# Main_Board.net
KiCad netlist of a schematic drawn in Altium Designer
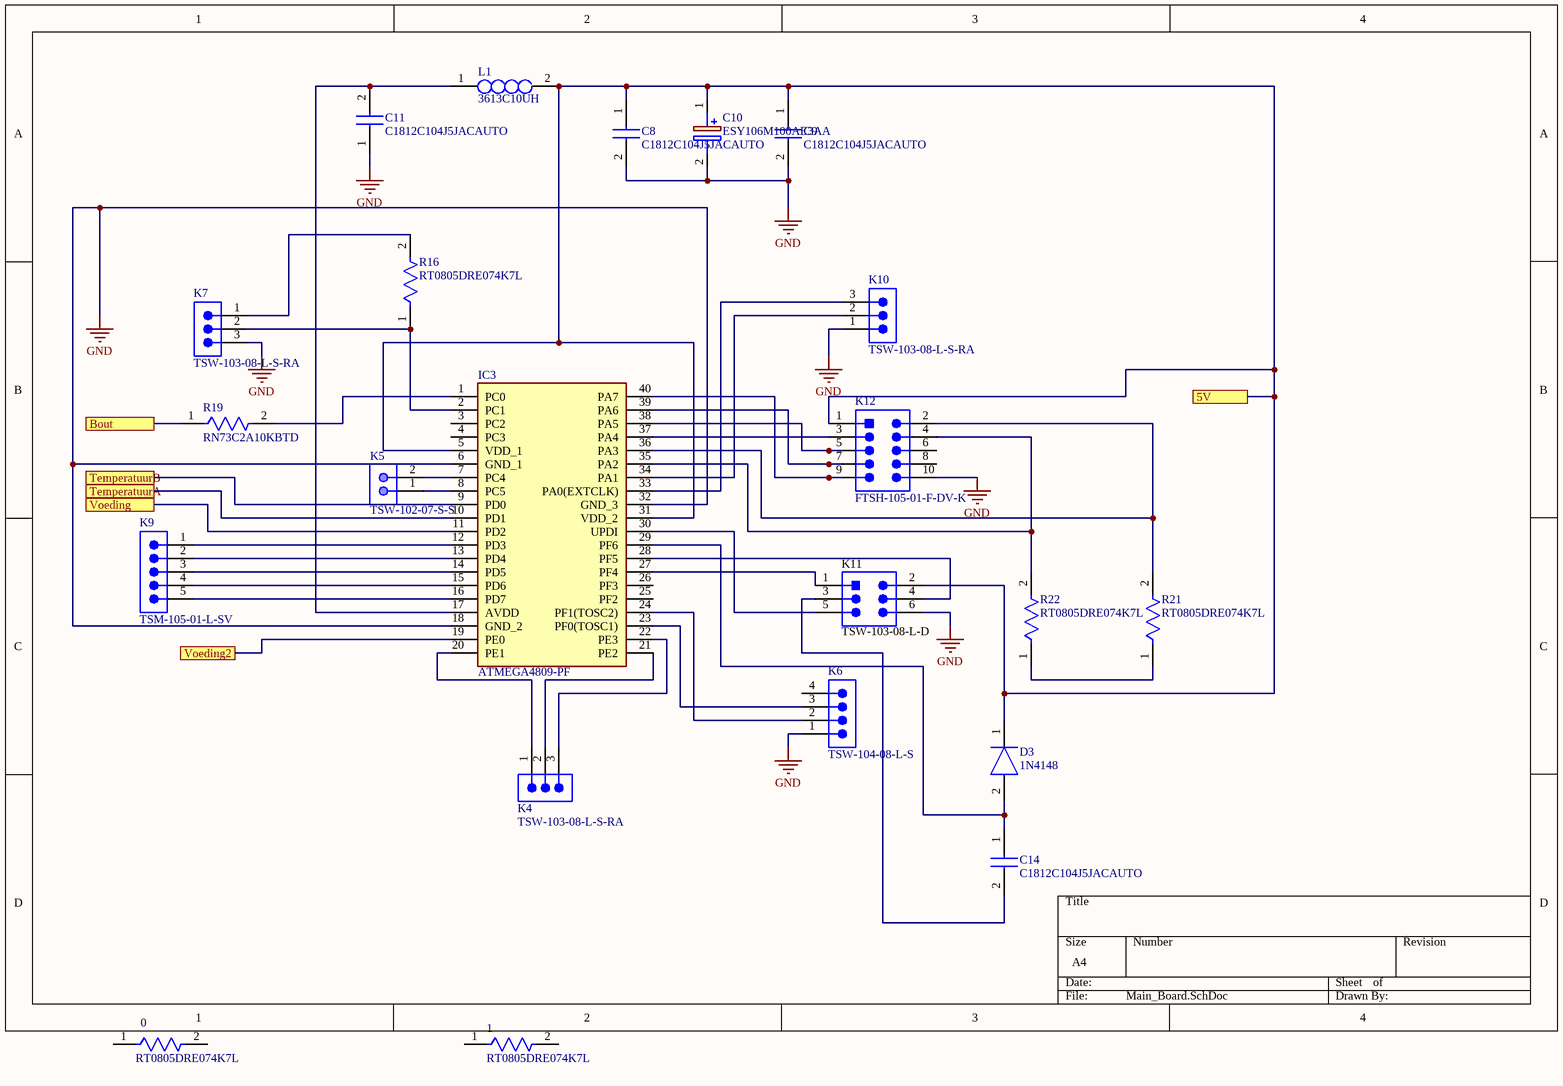
[diagram p0: Main_Board.SchDoc]

(export (version "E")
  (design (tool "Eeschema 10.0.6"))
  (components
    (comp (ref "0")
      (value "RT0805DRE074K7L")
      (footprint "FP-RT0805-MFG")
      (description "RES SMD 4.7K OHM 0.5% 1/8W 0805")
      (fields
        (field (name "OCTOPART") "https://octopart.com/rt0805dre074k7l-yageo-1242027")
        (field (name "TOLERANCE") "0.01")
      )
      (libsource (lib "Altium Content Vault") (part "1029c3af85768c4190bb7ad29bc67b5"))
    )
    (comp (ref "1")
      (value "RT0805DRE074K7L")
      (footprint "FP-RT0805-MFG")
      (description "RES SMD 4.7K OHM 0.5% 1/8W 0805")
      (fields
        (field (name "OCTOPART") "https://octopart.com/rt0805dre074k7l-yageo-1242027")
        (field (name "TOLERANCE") "0.01")
      )
      (libsource (lib "Altium Content Vault") (part "1029c3af85768c4190bb7ad29bc67b5"))
    )
    (comp (ref "C8")
      (value "C1812C104J5JACAUTO")
      (footprint "SamacSys:CAPC4532X110N")
      (description "Capacitor")
      (libsource (lib "*") (part "C1812C104J5JACAUTO"))
    )
    (comp (ref "C9")
      (value "C1812C104J5JACAUTO")
      (footprint "SamacSys:CAPC4532X110N")
      (description "Capacitor")
      (libsource (lib "*") (part "C1812C104J5JACAUTO"))
    )
    (comp (ref "C10")
      (value "ESY106M100AE3AA")
      (footprint "SamacSys:CAPPRD250W50D630H1250")
      (description "Capacitor Polarised")
      (libsource (lib "*") (part "ESY106M100AE3AA"))
    )
    (comp (ref "C11")
      (value "C1812C104J5JACAUTO")
      (footprint "SamacSys:CAPC4532X110N")
      (description "Capacitor")
      (libsource (lib "*") (part "C1812C104J5JACAUTO"))
    )
    (comp (ref "C14")
      (value "C1812C104J5JACAUTO")
      (footprint "SamacSys:CAPC4532X110N")
      (description "Capacitor")
      (libsource (lib "*") (part "C1812C104J5JACAUTO"))
    )
    (comp (ref "D3")
      (value "1N4148")
      (footprint "SamacSys:DIOAD1165W56L425D185")
      (description "Diode")
      (libsource (lib "*") (part "1N4148"))
    )
    (comp (ref "IC3")
      (value "ATMEGA4809-PF")
      (footprint "SamacSys:DIP1543W58P254L5175H635Q40N")
      (description "Integrated Circuit")
      (fields (field (name "MOUSER2 PART NUMBER") "556-ATMEGA4809-PF"))
      (libsource (lib "*") (part "ATMEGA4809-PF"))
    )
    (comp (ref "K4")
      (value "TSW-103-08-L-S-RA")
      (footprint "SMTC-TSW-103-08-X-S-RA")
      (fields (field (name "MANUFACTURER") "Samtec"))
      (libsource (lib "Altium Content Vault") (part "SMTC-TSW-103-X-X-S-X"))
    )
    (comp (ref "K5")
      (value "TSW-102-07-S-S")
      (footprint "SMTC-TSW-102-07-S-S")
      (fields (field (name "MANUFACTURER") "Samtec"))
      (libsource (lib "Altium Content Vault") (part "CN-1P-M-R2"))
    )
    (comp (ref "K6")
      (value "TSW-104-08-L-S")
      (footprint "SMTC-TSW-104-08-X-S")
      (description "0.025\" SQ Post Header, Through-hole, Vertical, -55 to 125 degC, 2.54 mm Pitch, 4-Pin, Male, RoHS")
      (fields (field (name "MANUFACTURER") "Samtec"))
      (libsource (lib "Altium Content Vault") (part "SMTC-TSW-104-08-X-S"))
    )
    (comp (ref "K7")
      (value "TSW-103-08-L-S-RA")
      (footprint "SMTC-TSW-103-08-X-S-RA")
      (fields (field (name "MANUFACTURER") "Samtec"))
      (libsource (lib "Altium Content Vault") (part "SMTC-TSW-103-X-X-S-X"))
    )
    (comp (ref "K9")
      (value "TSM-105-01-L-SV")
      (footprint "SMTC-TSM-105-01-X-SV")
      (description "0.025\" SQ Post Header, Surface Mount, Vertical, -55 to 125 degC, 2.54 mm Pitch, 5-Pin, Male, RoHS")
      (fields (field (name "MANUFACTURER") "Samtec"))
      (libsource (lib "Altium Content Vault") (part "SMTC-TSM-105-01-X-SV"))
    )
    (comp (ref "K10")
      (value "TSW-103-08-L-S-RA")
      (footprint "SMTC-TSW-103-08-X-S-RA")
      (fields (field (name "MANUFACTURER") "Samtec"))
      (libsource (lib "Altium Content Vault") (part "SMTC-TSW-103-X-X-S-X"))
    )
    (comp (ref "K11")
      (value "TSW-103-08-L-D")
      (footprint "SMTC-TSW-103-08-L-D_V")
      (fields (field (name "MANUFACTURER") "Samtec"))
      (libsource (lib "Altium Content Vault") (part "CN-2P-M-R6"))
    )
    (comp (ref "K12")
      (value "FTSH-105-01-F-DV-K")
      (footprint "SMTC-FTSH-105-01-L-DV-K_V")
      (description "Male Header, Pitch 1.27 mm, 2 x 5 Position, Height 6.12 mm, RoHS, Tube")
      (fields (field (name "MANUFACTURER") "Samtec"))
      (libsource (lib "Altium Content Vault") (part "CN-2P-M-R10"))
    )
    (comp (ref "L1")
      (value "3613C10UH")
      (footprint "SamacSys:INDM4532X340N")
      (description "Inductor")
      (libsource (lib "*") (part "3613C10UH"))
    )
    (comp (ref "R16")
      (value "RT0805DRE074K7L")
      (footprint "FP-RT0805-MFG")
      (description "RES SMD 4.7K OHM 0.5% 1/8W 0805")
      (fields
        (field (name "OCTOPART") "https://octopart.com/rt0805dre074k7l-yageo-1242027")
        (field (name "TOLERANCE") "0.01")
      )
      (libsource (lib "Altium Content Vault") (part "1029c3af85768c4190bb7ad29bc67b5"))
    )
    (comp (ref "R19")
      (value "RN73C2A10KBTD")
      (footprint "FP-RN732A-MFG")
      (description "SMD Chip Resistor, Thin Film, 10KΩ, 100 V, 0805 [2012 Metric], 100 mW, 0.1%, RN73 Series")
      (fields
        (field (name "MANUFACTURER") "TE Connectivity")
        (field (name "OCTOPART") "https://octopart.com/rn73c2a10kbtd-te+connectivity-22737006")
      )
      (libsource (lib "Altium Content Vault") (part "1029c3af85768c4190bb7ad29bc67b5"))
    )
    (comp (ref "R21")
      (value "RT0805DRE074K7L")
      (footprint "FP-RT0805-MFG")
      (description "RES SMD 4.7K OHM 0.5% 1/8W 0805")
      (fields
        (field (name "OCTOPART") "https://octopart.com/rt0805dre074k7l-yageo-1242027")
        (field (name "TOLERANCE") "0.01")
      )
      (libsource (lib "Altium Content Vault") (part "1029c3af85768c4190bb7ad29bc67b5"))
    )
    (comp (ref "R22")
      (value "RT0805DRE074K7L")
      (footprint "FP-RT0805-MFG")
      (description "RES SMD 4.7K OHM 0.5% 1/8W 0805")
      (fields
        (field (name "OCTOPART") "https://octopart.com/rt0805dre074k7l-yageo-1242027")
        (field (name "TOLERANCE") "0.01")
      )
      (libsource (lib "Altium Content Vault") (part "1029c3af85768c4190bb7ad29bc67b5"))
    )
  )
  (nets
    (net (code "1") (name "/5V") (class "Default")
      (node (ref "C10") (pin "1") (pinfunction "+_1") (pintype "passive"))
      (node (ref "C8") (pin "1") (pinfunction "1_1") (pintype "passive"))
      (node (ref "C9") (pin "1") (pinfunction "1_1") (pintype "passive"))
      (node (ref "D3") (pin "1") (pinfunction "K_1") (pintype "passive"))
      (node (ref "IC3") (pin "31") (pinfunction "VDD_2_31") (pintype "passive"))
      (node (ref "IC3") (pin "5") (pinfunction "VDD_1_5") (pintype "passive"))
      (node (ref "K11") (pin "2") (pinfunction "2_2") (pintype "passive"))
      (node (ref "K12") (pin "1") (pinfunction "1_1") (pintype "passive"))
      (node (ref "L1") (pin "2") (pinfunction "2_2") (pintype "passive"))
    )
    (net (code "2") (name "/Bout") (class "Default")
      (node (ref "R19") (pin "1") (pinfunction "1_1") (pintype "passive"))
    )
    (net (code "3") (name "/TemperatuurA") (class "Default")
      (node (ref "IC3") (pin "10") (pinfunction "PD1_10") (pintype "passive"))
    )
    (net (code "4") (name "/TemperatuurB") (class "Default")
      (node (ref "IC3") (pin "9") (pinfunction "PD0_9") (pintype "passive"))
    )
    (net (code "5") (name "/Voeding") (class "Default")
      (node (ref "IC3") (pin "11") (pinfunction "PD2_11") (pintype "passive"))
    )
    (net (code "6") (name "/Voeding2") (class "Default")
      (node (ref "IC3") (pin "19") (pinfunction "PE0_19") (pintype "passive"))
    )
    (net (code "7") (name "GND") (class "Default")
      (node (ref "C10") (pin "2") (pinfunction "-_2") (pintype "passive"))
      (node (ref "C11") (pin "1") (pinfunction "1_1") (pintype "passive"))
      (node (ref "C8") (pin "2") (pinfunction "2_2") (pintype "passive"))
      (node (ref "C9") (pin "2") (pinfunction "2_2") (pintype "passive"))
      (node (ref "IC3") (pin "18") (pinfunction "GND_2_18") (pintype "passive"))
      (node (ref "IC3") (pin "32") (pinfunction "GND_3_32") (pintype "passive"))
      (node (ref "IC3") (pin "6") (pinfunction "GND_1_6") (pintype "passive"))
      (node (ref "K10") (pin "1") (pinfunction "1_1") (pintype "passive"))
      (node (ref "K11") (pin "6") (pinfunction "6_6") (pintype "passive"))
      (node (ref "K12") (pin "10") (pinfunction "10_10") (pintype "passive"))
      (node (ref "K6") (pin "1") (pinfunction "1_1") (pintype "passive"))
      (node (ref "K7") (pin "3") (pinfunction "3_3") (pintype "passive"))
    )
    (net (code "8") (name "Net-(C14-Pad2)") (class "Default")
      (node (ref "C14") (pin "2") (pinfunction "2_2") (pintype "passive"))
      (node (ref "K11") (pin "3") (pinfunction "3_3") (pintype "passive"))
    )
    (net (code "9") (name "Net-(D3-A)") (class "Default")
      (node (ref "C14") (pin "1") (pinfunction "1_1") (pintype "passive"))
      (node (ref "D3") (pin "2") (pinfunction "A_2") (pintype "passive"))
      (node (ref "IC3") (pin "29") (pinfunction "PF6_29") (pintype "passive"))
    )
    (net (code "10") (name "Net-(IC3-AVDD)") (class "Default")
      (node (ref "C11") (pin "2") (pinfunction "2_2") (pintype "passive"))
      (node (ref "IC3") (pin "17") (pinfunction "AVDD_17") (pintype "passive"))
      (node (ref "L1") (pin "1") (pinfunction "1_1") (pintype "passive"))
    )
    (net (code "11") (name "Net-(IC3-PA0(EXTCLK))") (class "Default")
      (node (ref "IC3") (pin "33") (pinfunction "PA0(EXTCLK)_33") (pintype "passive"))
      (node (ref "K10") (pin "3") (pinfunction "3_3") (pintype "passive"))
    )
    (net (code "12") (name "Net-(IC3-PA1)") (class "Default")
      (node (ref "IC3") (pin "34") (pinfunction "PA1_34") (pintype "passive"))
      (node (ref "K10") (pin "2") (pinfunction "2_2") (pintype "passive"))
    )
    (net (code "13") (name "Net-(IC3-PA2)") (class "Default")
      (node (ref "IC3") (pin "35") (pinfunction "PA2_35") (pintype "passive"))
      (node (ref "K12") (pin "4") (pinfunction "4_4") (pintype "passive"))
      (node (ref "R22") (pin "2") (pinfunction "2_2") (pintype "passive"))
    )
    (net (code "14") (name "Net-(IC3-PA3)") (class "Default")
      (node (ref "IC3") (pin "36") (pinfunction "PA3_36") (pintype "passive"))
      (node (ref "K12") (pin "2") (pinfunction "2_2") (pintype "passive"))
      (node (ref "R21") (pin "2") (pinfunction "2_2") (pintype "passive"))
    )
    (net (code "15") (name "Net-(IC3-PA4)") (class "Default")
      (node (ref "IC3") (pin "37") (pinfunction "PA4_37") (pintype "passive"))
      (node (ref "K12") (pin "3") (pinfunction "3_3") (pintype "passive"))
    )
    (net (code "16") (name "Net-(IC3-PA5)") (class "Default")
      (node (ref "IC3") (pin "38") (pinfunction "PA5_38") (pintype "passive"))
      (node (ref "K12") (pin "5") (pinfunction "5_5") (pintype "passive"))
    )
    (net (code "17") (name "Net-(IC3-PA6)") (class "Default")
      (node (ref "IC3") (pin "39") (pinfunction "PA6_39") (pintype "passive"))
      (node (ref "K12") (pin "7") (pinfunction "7_7") (pintype "passive"))
    )
    (net (code "18") (name "Net-(IC3-PA7)") (class "Default")
      (node (ref "IC3") (pin "40") (pinfunction "PA7_40") (pintype "passive"))
      (node (ref "K12") (pin "9") (pinfunction "9_9") (pintype "passive"))
    )
    (net (code "19") (name "Net-(IC3-PC0)") (class "Default")
      (node (ref "IC3") (pin "1") (pinfunction "PC0_1") (pintype "passive"))
      (node (ref "R19") (pin "2") (pinfunction "2_2") (pintype "passive"))
    )
    (net (code "20") (name "Net-(IC3-PC1)") (class "Default")
      (node (ref "IC3") (pin "2") (pinfunction "PC1_2") (pintype "passive"))
      (node (ref "K7") (pin "2") (pinfunction "2_2") (pintype "passive"))
      (node (ref "R16") (pin "1") (pinfunction "1_1") (pintype "passive"))
    )
    (net (code "21") (name "Net-(IC3-PC4)") (class "Default")
      (node (ref "IC3") (pin "7") (pinfunction "PC4_7") (pintype "passive"))
      (node (ref "K5") (pin "2") (pinfunction "2_2") (pintype "passive"))
    )
    (net (code "22") (name "Net-(IC3-PC5)") (class "Default")
      (node (ref "IC3") (pin "8") (pinfunction "PC5_8") (pintype "passive"))
      (node (ref "K5") (pin "1") (pinfunction "1_1") (pintype "passive"))
    )
    (net (code "23") (name "Net-(IC3-PD3)") (class "Default")
      (node (ref "IC3") (pin "12") (pinfunction "PD3_12") (pintype "passive"))
      (node (ref "K9") (pin "1") (pinfunction "1_1") (pintype "passive"))
    )
    (net (code "24") (name "Net-(IC3-PD4)") (class "Default")
      (node (ref "IC3") (pin "13") (pinfunction "PD4_13") (pintype "passive"))
      (node (ref "K9") (pin "2") (pinfunction "2_2") (pintype "passive"))
    )
    (net (code "25") (name "Net-(IC3-PD5)") (class "Default")
      (node (ref "IC3") (pin "14") (pinfunction "PD5_14") (pintype "passive"))
      (node (ref "K9") (pin "3") (pinfunction "3_3") (pintype "passive"))
    )
    (net (code "26") (name "Net-(IC3-PD6)") (class "Default")
      (node (ref "IC3") (pin "15") (pinfunction "PD6_15") (pintype "passive"))
      (node (ref "K9") (pin "4") (pinfunction "4_4") (pintype "passive"))
    )
    (net (code "27") (name "Net-(IC3-PD7)") (class "Default")
      (node (ref "IC3") (pin "16") (pinfunction "PD7_16") (pintype "passive"))
      (node (ref "K9") (pin "5") (pinfunction "5_5") (pintype "passive"))
    )
    (net (code "28") (name "Net-(IC3-PE1)") (class "Default")
      (node (ref "IC3") (pin "20") (pinfunction "PE1_20") (pintype "passive"))
      (node (ref "K4") (pin "1") (pinfunction "1_1") (pintype "passive"))
    )
    (net (code "29") (name "Net-(IC3-PE2)") (class "Default")
      (node (ref "IC3") (pin "21") (pinfunction "PE2_21") (pintype "passive"))
      (node (ref "K4") (pin "2") (pinfunction "2_2") (pintype "passive"))
    )
    (net (code "30") (name "Net-(IC3-PE3)") (class "Default")
      (node (ref "IC3") (pin "22") (pinfunction "PE3_22") (pintype "passive"))
      (node (ref "K4") (pin "3") (pinfunction "3_3") (pintype "passive"))
    )
    (net (code "31") (name "Net-(IC3-PF0(TOSC1))") (class "Default")
      (node (ref "IC3") (pin "23") (pinfunction "PF0(TOSC1)_23") (pintype "passive"))
      (node (ref "K6") (pin "3") (pinfunction "3_3") (pintype "passive"))
    )
    (net (code "32") (name "Net-(IC3-PF1(TOSC2))") (class "Default")
      (node (ref "IC3") (pin "24") (pinfunction "PF1(TOSC2)_24") (pintype "passive"))
      (node (ref "K6") (pin "2") (pinfunction "2_2") (pintype "passive"))
    )
    (net (code "33") (name "Net-(IC3-PF4)") (class "Default")
      (node (ref "IC3") (pin "27") (pinfunction "PF4_27") (pintype "passive"))
      (node (ref "K11") (pin "1") (pinfunction "1_1") (pintype "passive"))
    )
    (net (code "34") (name "Net-(IC3-PF5)") (class "Default")
      (node (ref "IC3") (pin "28") (pinfunction "PF5_28") (pintype "passive"))
      (node (ref "K11") (pin "4") (pinfunction "4_4") (pintype "passive"))
    )
    (net (code "35") (name "Net-(IC3-UPDI)") (class "Default")
      (node (ref "IC3") (pin "30") (pinfunction "UPDI_30") (pintype "passive"))
      (node (ref "K11") (pin "5") (pinfunction "5_5") (pintype "passive"))
    )
    (net (code "36") (name "Net-(K7-Pad1)") (class "Default")
      (node (ref "K7") (pin "1") (pinfunction "1_1") (pintype "passive"))
      (node (ref "R16") (pin "2") (pinfunction "2_2") (pintype "passive"))
    )
    (net (code "37") (name "Net-(R21-Pad1)") (class "Default")
      (node (ref "R21") (pin "1") (pinfunction "1_1") (pintype "passive"))
      (node (ref "R22") (pin "1") (pinfunction "1_1") (pintype "passive"))
    )
    (net (code "38") (name "unconnected-(0-Pad1)") (class "Default")
      (node (ref "0") (pin "1") (pinfunction "1_1") (pintype "passive"))
    )
    (net (code "39") (name "unconnected-(0-Pad2)") (class "Default")
      (node (ref "0") (pin "2") (pinfunction "2_2") (pintype "passive"))
    )
    (net (code "40") (name "unconnected-(1-Pad1)") (class "Default")
      (node (ref "1") (pin "1") (pinfunction "1_1") (pintype "passive"))
    )
    (net (code "41") (name "unconnected-(1-Pad2)") (class "Default")
      (node (ref "1") (pin "2") (pinfunction "2_2") (pintype "passive"))
    )
    (net (code "42") (name "unconnected-(IC3-PC2-Pad3)") (class "Default")
      (node (ref "IC3") (pin "3") (pinfunction "PC2_3") (pintype "passive"))
    )
    (net (code "43") (name "unconnected-(IC3-PC3-Pad4)") (class "Default")
      (node (ref "IC3") (pin "4") (pinfunction "PC3_4") (pintype "passive"))
    )
    (net (code "44") (name "unconnected-(IC3-PF2-Pad25)") (class "Default")
      (node (ref "IC3") (pin "25") (pinfunction "PF2_25") (pintype "passive"))
    )
    (net (code "45") (name "unconnected-(IC3-PF3-Pad26)") (class "Default")
      (node (ref "IC3") (pin "26") (pinfunction "PF3_26") (pintype "passive"))
    )
    (net (code "46") (name "unconnected-(K6-Pad4)") (class "Default")
      (node (ref "K6") (pin "4") (pinfunction "4_4") (pintype "passive"))
    )
    (net (code "47") (name "unconnected-(K12-Pad6)") (class "Default")
      (node (ref "K12") (pin "6") (pinfunction "6_6") (pintype "passive"))
    )
    (net (code "48") (name "unconnected-(K12-Pad8)") (class "Default")
      (node (ref "K12") (pin "8") (pinfunction "8_8") (pintype "passive"))
    )
  )
)
